# SensorSuite.net
KiCad netlist of a schematic drawn in Altium Designer
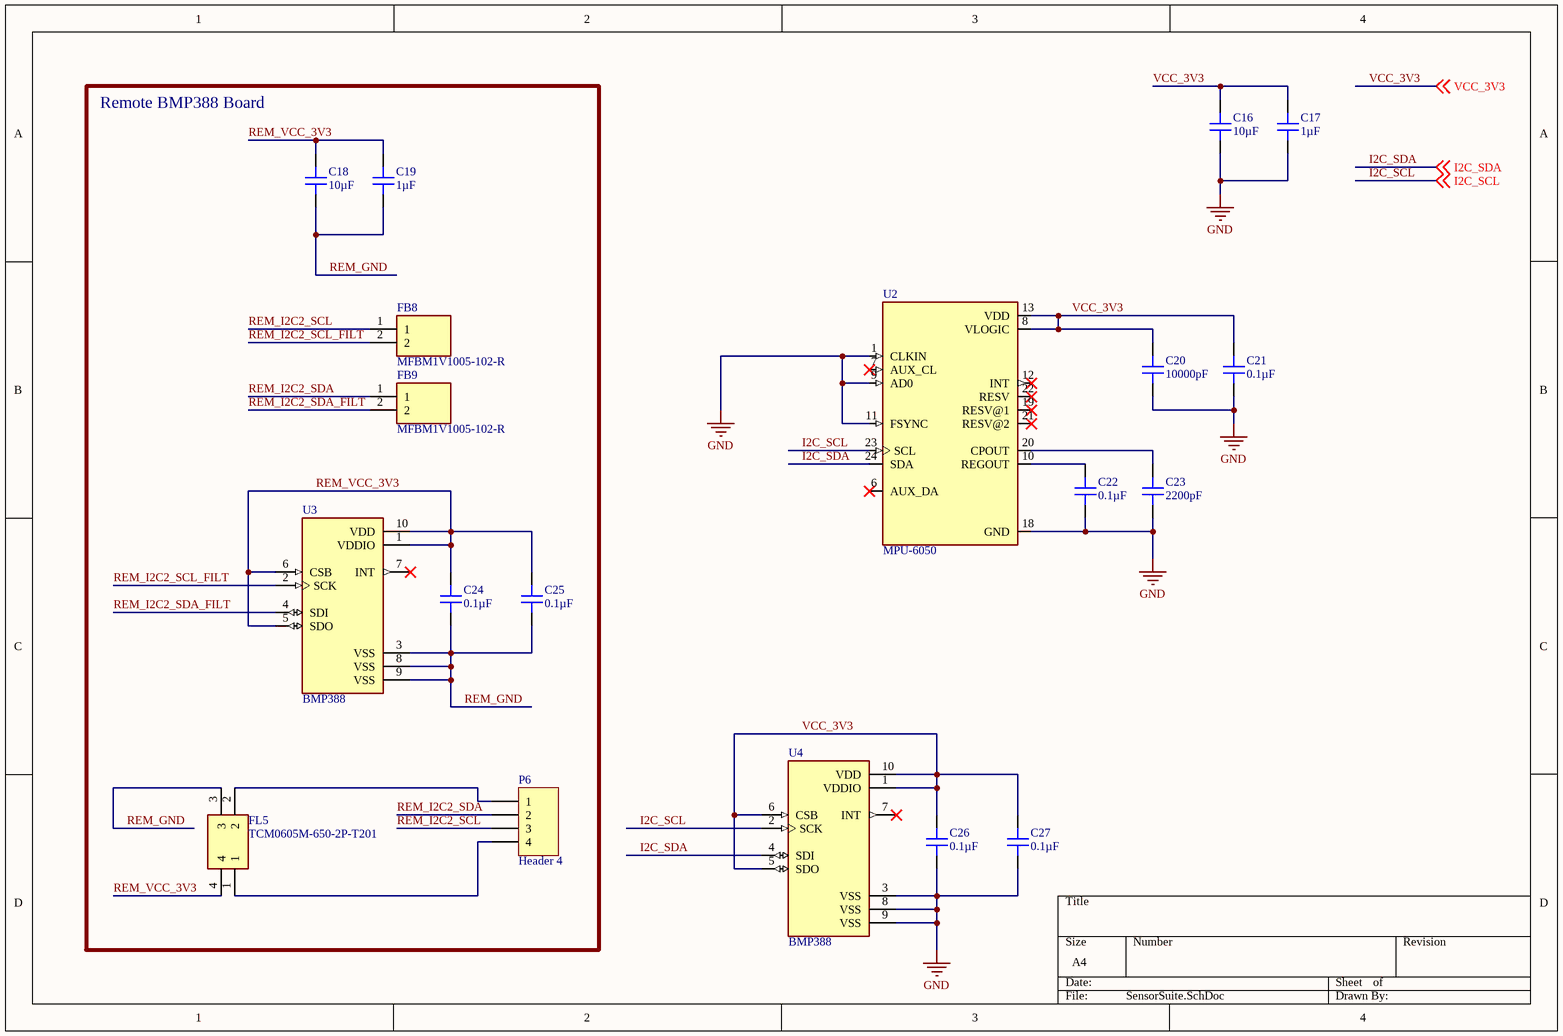
[diagram p0: SensorSuite.SchDoc]

(export (version "E")
  (design (tool "Eeschema 10.0.6"))
  (components
    (comp (ref "C16")
      (value "10µF")
      (footprint "CAP 0402_1005")
      (description "CAP CER 10UF 6.3V X5R 0402")
      (fields (field (name "PART NUMBER") "C0402C106M9PAC7867") (field (name "MANUFACTURER") "KEMET"))
      (libsource (lib "Celestial Altium Library - altium_library") (part "Capacitor"))
    )
    (comp (ref "C17")
      (value "1µF")
      (footprint "CAP 0402_1005")
      (description "CAP CER 1UF 16V X5R 0402")
      (fields (field (name "PART NUMBER") "0402YD105KAT2A") (field (name "MANUFACTURER") "AVX Corporation"))
      (libsource (lib "Celestial Altium Library - altium_library") (part "Capacitor"))
    )
    (comp (ref "C18")
      (value "10µF")
      (footprint "CAP 0402_1005")
      (description "CAP CER 10UF 6.3V X5R 0402")
      (fields (field (name "PART NUMBER") "C0402C106M9PAC7867") (field (name "MANUFACTURER") "KEMET"))
      (libsource (lib "Celestial Altium Library - altium_library") (part "Capacitor"))
    )
    (comp (ref "C19")
      (value "1µF")
      (footprint "CAP 0402_1005")
      (description "CAP CER 1UF 16V X5R 0402")
      (fields (field (name "PART NUMBER") "0402YD105KAT2A") (field (name "MANUFACTURER") "AVX Corporation"))
      (libsource (lib "Celestial Altium Library - altium_library") (part "Capacitor"))
    )
    (comp (ref "C20")
      (value "10000pF")
      (footprint "CAP 0402_1005")
      (description "CAP CER 10000PF 50V X7R 0402")
      (fields
        (field (name "PART NUMBER") "0402B103K500CT")
        (field (name "MANUFACTURER") "Walsin Technology Corporation")
      )
      (libsource (lib "Celestial Altium Library - altium_library") (part "Capacitor"))
    )
    (comp (ref "C21")
      (value "0.1µF")
      (footprint "CAP 0402_1005")
      (description "CAP CER 0.1UF 6.3V X5R 0402")
      (fields (field (name "PART NUMBER") "C0402C104K9PACTU") (field (name "MANUFACTURER") "KEMET"))
      (libsource (lib "Celestial Altium Library - altium_library") (part "Capacitor"))
    )
    (comp (ref "C22")
      (value "0.1µF")
      (footprint "CAP 0402_1005")
      (description "CAP CER 0.1UF 6.3V X5R 0402")
      (fields (field (name "PART NUMBER") "C0402C104K9PACTU") (field (name "MANUFACTURER") "KEMET"))
      (libsource (lib "Celestial Altium Library - altium_library") (part "Capacitor"))
    )
    (comp (ref "C23")
      (value "2200pF")
      (footprint "CAP 0402_1005")
      (description "CAP CER 2200PF 50V X7R 0402")
      (fields
        (field (name "PART NUMBER") "0402B222K500CT")
        (field (name "MANUFACTURER") "Walsin Technology Corporation")
      )
      (libsource (lib "Celestial Altium Library - altium_library") (part "Capacitor"))
    )
    (comp (ref "C24")
      (value "0.1µF")
      (footprint "CAP 0402_1005")
      (description "CAP CER 0.1UF 6.3V X5R 0402")
      (fields (field (name "PART NUMBER") "C0402C104K9PACTU") (field (name "MANUFACTURER") "KEMET"))
      (libsource (lib "Celestial Altium Library - altium_library") (part "Capacitor"))
    )
    (comp (ref "C25")
      (value "0.1µF")
      (footprint "CAP 0402_1005")
      (description "CAP CER 0.1UF 6.3V X5R 0402")
      (fields (field (name "PART NUMBER") "C0402C104K9PACTU") (field (name "MANUFACTURER") "KEMET"))
      (libsource (lib "Celestial Altium Library - altium_library") (part "Capacitor"))
    )
    (comp (ref "C26")
      (value "0.1µF")
      (footprint "CAP 0402_1005")
      (description "CAP CER 0.1UF 6.3V X5R 0402")
      (fields (field (name "PART NUMBER") "C0402C104K9PACTU") (field (name "MANUFACTURER") "KEMET"))
      (libsource (lib "Celestial Altium Library - altium_library") (part "Capacitor"))
    )
    (comp (ref "C27")
      (value "0.1µF")
      (footprint "CAP 0402_1005")
      (description "CAP CER 0.1UF 6.3V X5R 0402")
      (fields (field (name "PART NUMBER") "C0402C104K9PACTU") (field (name "MANUFACTURER") "KEMET"))
      (libsource (lib "Celestial Altium Library - altium_library") (part "Capacitor"))
    )
    (comp (ref "FB8")
      (value "MFBM1V1005-102-R")
      (footprint "SamacSys:BEADC1005X65N")
      (description "Ferrite Bead")
      (fields (field (name "MANUFACTURER_PART_NUMBER") "MFBM1V1005-101-R"))
      (libsource (lib "SamacSys") (part "MFBM1V1005-102-R"))
    )
    (comp (ref "FB9")
      (value "MFBM1V1005-102-R")
      (footprint "SamacSys:BEADC1005X65N")
      (description "Ferrite Bead")
      (fields (field (name "MANUFACTURER_PART_NUMBER") "MFBM1V1005-101-R"))
      (libsource (lib "SamacSys") (part "MFBM1V1005-102-R"))
    )
    (comp (ref "FL5")
      (value "TCM0605M-650-2P-T201")
      (footprint "SamacSys:TCM0605M")
      (description "Filter")
      (libsource (lib "*") (part "TCM0605M-650-2P-T201"))
    )
    (comp (ref "P6")
      (value "Header 4")
      (footprint "HDR1X4")
      (description "Header, 4-Pin")
      (fields (field (name "PUBLISHER") "Altium Limited"))
      (libsource (lib "Miscellaneous Connectors") (part "Header 4"))
    )
    (comp (ref "U2")
      (value "MPU-6050")
      (footprint "QFN50P400X400X95-24N")
      (description "Accelerometer, Gyroscope, 6 Axis Sensor IÂ²C Output")
      (fields (field (name "MF") "TDK InvenSense"))
      (libsource (lib "MPU-6050") (part "MPU-6050"))
    )
    (comp (ref "U3")
      (value "BMP388")
      (footprint "PQFN50P200X200X80-10N")
      (description "Pressure Sensor 4.35PSI ~ 18.13PSI _30kPa ~ 125kPa_ Absolute 10-WFLGA")
      (fields (field (name "DIGI-KEY_PART_NUMBER") "828-1079-1-ND") (field (name "MF") "Bosch Sensortec"))
      (libsource (lib "BMP388") (part "BMP388"))
    )
    (comp (ref "U4")
      (value "BMP388")
      (footprint "PQFN50P200X200X80-10N")
      (description "Pressure Sensor 4.35PSI ~ 18.13PSI _30kPa ~ 125kPa_ Absolute 10-WFLGA")
      (fields (field (name "DIGI-KEY_PART_NUMBER") "828-1079-1-ND") (field (name "MF") "Bosch Sensortec"))
      (libsource (lib "BMP388") (part "BMP388"))
    )
  )
  (nets
    (net (code "1") (name "/REM_GND") (class "Default")
      (node (ref "C18") (pin "1") (pinfunction "1_1") (pintype "passive"))
      (node (ref "C19") (pin "1") (pinfunction "1_1") (pintype "passive"))
      (node (ref "C24") (pin "1") (pinfunction "1_1") (pintype "passive"))
      (node (ref "C25") (pin "1") (pinfunction "1_1") (pintype "passive"))
      (node (ref "FL5") (pin "3") (pinfunction "3_3") (pintype "passive"))
      (node (ref "U3") (pin "3") (pinfunction "VSS_3") (pintype "power_in"))
      (node (ref "U3") (pin "8") (pinfunction "VSS_8") (pintype "power_in"))
      (node (ref "U3") (pin "9") (pinfunction "VSS_9") (pintype "power_in"))
    )
    (net (code "2") (name "/REM_I2C2_SCL") (class "Default")
      (node (ref "FB8") (pin "1") (pinfunction "1_1") (pintype "passive"))
      (node (ref "P6") (pin "3") (pinfunction "3_3") (pintype "passive"))
    )
    (net (code "3") (name "/REM_I2C2_SCL_FILT") (class "Default")
      (node (ref "FB8") (pin "2") (pinfunction "2_2") (pintype "passive"))
      (node (ref "U3") (pin "2") (pinfunction "SCK_2") (pintype "input"))
    )
    (net (code "4") (name "/REM_I2C2_SDA") (class "Default")
      (node (ref "FB9") (pin "1") (pinfunction "1_1") (pintype "passive"))
      (node (ref "P6") (pin "2") (pinfunction "2_2") (pintype "passive"))
    )
    (net (code "5") (name "/REM_I2C2_SDA_FILT") (class "Default")
      (node (ref "FB9") (pin "2") (pinfunction "2_2") (pintype "passive"))
      (node (ref "U3") (pin "4") (pinfunction "SDI_4") (pintype "bidirectional"))
    )
    (net (code "6") (name "/REM_VCC_3V3") (class "Default")
      (node (ref "C18") (pin "2") (pinfunction "2_2") (pintype "passive"))
      (node (ref "C19") (pin "2") (pinfunction "2_2") (pintype "passive"))
      (node (ref "C24") (pin "2") (pinfunction "2_2") (pintype "passive"))
      (node (ref "C25") (pin "2") (pinfunction "2_2") (pintype "passive"))
      (node (ref "FL5") (pin "4") (pinfunction "4_4") (pintype "passive"))
      (node (ref "U3") (pin "1") (pinfunction "VDDIO_1") (pintype "power_in"))
      (node (ref "U3") (pin "10") (pinfunction "VDD_10") (pintype "power_in"))
      (node (ref "U3") (pin "5") (pinfunction "SDO_5") (pintype "bidirectional"))
      (node (ref "U3") (pin "6") (pinfunction "CSB_6") (pintype "input"))
    )
    (net (code "7") (name "GND") (class "Default")
      (node (ref "C16") (pin "1") (pinfunction "1_1") (pintype "passive"))
      (node (ref "C17") (pin "1") (pinfunction "1_1") (pintype "passive"))
      (node (ref "C20") (pin "1") (pinfunction "1_1") (pintype "passive"))
      (node (ref "C21") (pin "1") (pinfunction "1_1") (pintype "passive"))
      (node (ref "C22") (pin "1") (pinfunction "1_1") (pintype "passive"))
      (node (ref "C23") (pin "1") (pinfunction "1_1") (pintype "passive"))
      (node (ref "C26") (pin "1") (pinfunction "1_1") (pintype "passive"))
      (node (ref "C27") (pin "1") (pinfunction "1_1") (pintype "passive"))
      (node (ref "U2") (pin "1") (pinfunction "CLKIN_1") (pintype "input"))
      (node (ref "U2") (pin "11") (pinfunction "FSYNC_11") (pintype "input"))
      (node (ref "U2") (pin "18") (pinfunction "GND_18") (pintype "power_in"))
      (node (ref "U2") (pin "9") (pinfunction "AD0_9") (pintype "input"))
      (node (ref "U4") (pin "3") (pinfunction "VSS_3") (pintype "power_in"))
      (node (ref "U4") (pin "8") (pinfunction "VSS_8") (pintype "power_in"))
      (node (ref "U4") (pin "9") (pinfunction "VSS_9") (pintype "power_in"))
    )
    (net (code "8") (name "I2C_SCL") (class "Default")
      (node (ref "U2") (pin "23") (pinfunction "SCL_23") (pintype "input"))
      (node (ref "U4") (pin "2") (pinfunction "SCK_2") (pintype "input"))
    )
    (net (code "9") (name "I2C_SDA") (class "Default")
      (node (ref "U2") (pin "24") (pinfunction "SDA_24") (pintype "bidirectional"))
      (node (ref "U4") (pin "4") (pinfunction "SDI_4") (pintype "bidirectional"))
    )
    (net (code "10") (name "Net-(FL5-Pad1)") (class "Default")
      (node (ref "FL5") (pin "1") (pinfunction "1_1") (pintype "passive"))
      (node (ref "P6") (pin "4") (pinfunction "4_4") (pintype "passive"))
    )
    (net (code "11") (name "Net-(FL5-Pad2)") (class "Default")
      (node (ref "FL5") (pin "2") (pinfunction "2_2") (pintype "passive"))
      (node (ref "P6") (pin "1") (pinfunction "1_1") (pintype "passive"))
    )
    (net (code "12") (name "Net-(U2-CPOUT)") (class "Default")
      (node (ref "C23") (pin "2") (pinfunction "2_2") (pintype "passive"))
      (node (ref "U2") (pin "20") (pinfunction "CPOUT_20") (pintype "passive"))
    )
    (net (code "13") (name "Net-(U2-REGOUT)") (class "Default")
      (node (ref "C22") (pin "2") (pinfunction "2_2") (pintype "passive"))
      (node (ref "U2") (pin "10") (pinfunction "REGOUT_10") (pintype "passive"))
    )
    (net (code "14") (name "VCC_3V3") (class "Default")
      (node (ref "C16") (pin "2") (pinfunction "2_2") (pintype "passive"))
      (node (ref "C17") (pin "2") (pinfunction "2_2") (pintype "passive"))
      (node (ref "C20") (pin "2") (pinfunction "2_2") (pintype "passive"))
      (node (ref "C21") (pin "2") (pinfunction "2_2") (pintype "passive"))
      (node (ref "C26") (pin "2") (pinfunction "2_2") (pintype "passive"))
      (node (ref "C27") (pin "2") (pinfunction "2_2") (pintype "passive"))
      (node (ref "U2") (pin "13") (pinfunction "VDD_13") (pintype "power_in"))
      (node (ref "U2") (pin "8") (pinfunction "VLOGIC_8") (pintype "power_in"))
      (node (ref "U4") (pin "1") (pinfunction "VDDIO_1") (pintype "power_in"))
      (node (ref "U4") (pin "10") (pinfunction "VDD_10") (pintype "power_in"))
      (node (ref "U4") (pin "5") (pinfunction "SDO_5") (pintype "bidirectional"))
      (node (ref "U4") (pin "6") (pinfunction "CSB_6") (pintype "input"))
    )
    (net (code "15") (name "unconnected-(U2-AUX_CL-Pad7)") (class "Default")
      (node (ref "U2") (pin "7") (pinfunction "AUX_CL_7") (pintype "input+no_connect"))
    )
    (net (code "16") (name "unconnected-(U2-AUX_DA-Pad6)") (class "Default")
      (node (ref "U2") (pin "6") (pinfunction "AUX_DA_6") (pintype "bidirectional+no_connect"))
    )
    (net (code "17") (name "unconnected-(U2-INT-Pad12)") (class "Default")
      (node (ref "U2") (pin "12") (pinfunction "INT_12") (pintype "output+no_connect"))
    )
    (net (code "18") (name "unconnected-(U2-RESV-Pad22)") (class "Default")
      (node (ref "U2") (pin "22") (pinfunction "RESV_22") (pintype "passive+no_connect"))
    )
    (net (code "19") (name "unconnected-(U2-RESV@1-Pad19)") (class "Default")
      (node (ref "U2") (pin "19") (pinfunction "RESV@1_19") (pintype "passive+no_connect"))
    )
    (net (code "20") (name "unconnected-(U2-RESV@2-Pad21)") (class "Default")
      (node (ref "U2") (pin "21") (pinfunction "RESV@2_21") (pintype "passive+no_connect"))
    )
    (net (code "21") (name "unconnected-(U3-INT-Pad7)") (class "Default")
      (node (ref "U3") (pin "7") (pinfunction "INT_7") (pintype "output+no_connect"))
    )
    (net (code "22") (name "unconnected-(U4-INT-Pad7)") (class "Default")
      (node (ref "U4") (pin "7") (pinfunction "INT_7") (pintype "output+no_connect"))
    )
  )
)
